# Sheet1.net
KiCad netlist of a schematic drawn in Altium Designer
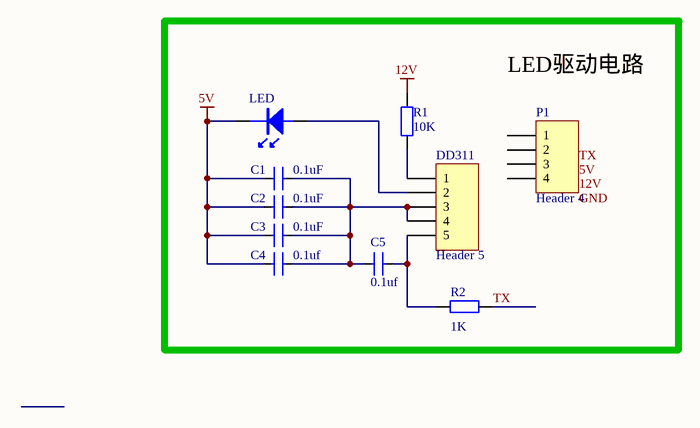
[diagram p0: Sheet1.SchDoc]

(export (version "E")
  (design (tool "Eeschema 10.0.6"))
  (components
    (comp (ref "C1")
      (value "0.1uF")
      (footprint "0805C")
      (description "SMD-CAP")
      (libsource (lib "RCDQLY") (part "C_0.1uF"))
    )
    (comp (ref "C2")
      (value "0.1uF")
      (footprint "0805C")
      (description "SMD-CAP")
      (libsource (lib "RCDQLY") (part "C_0.1uF"))
    )
    (comp (ref "C3")
      (value "0.1uF")
      (footprint "0805C")
      (description "SMD-CAP")
      (libsource (lib "RCDQLY") (part "C_0.1uF"))
    )
    (comp (ref "C4")
      (value "0.1uf")
      (footprint "0805C")
      (description "SMD-CAP")
      (libsource (lib "RCDQLY") (part "C_0.1uF"))
    )
    (comp (ref "C5")
      (value "0.1uf")
      (footprint "0805C")
      (description "SMD-CAP")
      (libsource (lib "RCDQLY") (part "C_0.1uF"))
    )
    (comp (ref "DD311")
      (value "Header 5")
      (footprint "DD311")
      (description "Header, 5-Pin")
      (fields (field (name "PUBLISHER") "Altium Limited"))
      (libsource (lib "Miscellaneous Connectors") (part "Header 5"))
    )
    (comp (ref "LED")
      (value "D-LED")
      (footprint "led")
      (description "LED")
      (libsource (lib "RCDQLY") (part "D-LED"))
    )
    (comp (ref "P1")
      (value "Header 4")
      (footprint "HDR1X4")
      (description "Header, 4-Pin")
      (fields (field (name "PUBLISHER") "Altium Limited"))
      (libsource (lib "Miscellaneous Connectors") (part "Header 4"))
    )
    (comp (ref "R1")
      (value "10K")
      (footprint "0805")
      (description "Resistor")
      (fields (field (name "Comment") "Res2") (field (name "PUBLISHER") "Altium Limited"))
      (libsource (lib "Miscellaneous Devices") (part "Res2"))
    )
    (comp (ref "R2")
      (value "1K")
      (footprint "0805")
      (description "Resistor")
      (fields (field (name "Comment") "Res2") (field (name "PUBLISHER") "Altium Limited"))
      (libsource (lib "") (part "Res2_1"))
    )
  )
  (nets
    (net (code "2") (name "/TX") (class "Default")
      (node (ref "R2") (pin "2") (pinfunction "2_2") (pintype "passive"))
    )
    (net (code "3") (name "5V") (class "Default")
      (node (ref "C1") (pin "1") (pinfunction "1_1") (pintype "passive"))
      (node (ref "C2") (pin "1") (pinfunction "1_1") (pintype "passive"))
      (node (ref "C3") (pin "1") (pinfunction "1_1") (pintype "passive"))
      (node (ref "C4") (pin "1") (pinfunction "1_1") (pintype "passive"))
      (node (ref "LED") (pin "K") (pinfunction "2_K") (pintype "passive"))
    )
    (net (code "4") (name "12V") (class "Default")
      (node (ref "R1") (pin "2") (pinfunction "2_2") (pintype "passive"))
    )
    (net (code "5") (name "Net-(C1-Pad2)") (class "Default")
      (node (ref "C1") (pin "2") (pinfunction "2_2") (pintype "passive"))
      (node (ref "C2") (pin "2") (pinfunction "2_2") (pintype "passive"))
      (node (ref "C3") (pin "2") (pinfunction "2_2") (pintype "passive"))
      (node (ref "C4") (pin "2") (pinfunction "2_2") (pintype "passive"))
      (node (ref "C5") (pin "1") (pinfunction "1_1") (pintype "passive"))
      (node (ref "DD311") (pin "3") (pinfunction "3_3") (pintype "passive"))
      (node (ref "DD311") (pin "4") (pinfunction "4_4") (pintype "passive"))
    )
    (net (code "6") (name "Net-(C5-Pad2)") (class "Default")
      (node (ref "C5") (pin "2") (pinfunction "2_2") (pintype "passive"))
      (node (ref "DD311") (pin "5") (pinfunction "5_5") (pintype "passive"))
      (node (ref "R2") (pin "1") (pinfunction "1_1") (pintype "passive"))
    )
    (net (code "7") (name "Net-(DD311-Pad1)") (class "Default")
      (node (ref "DD311") (pin "1") (pinfunction "1_1") (pintype "passive"))
      (node (ref "R1") (pin "1") (pinfunction "1_1") (pintype "passive"))
    )
    (net (code "8") (name "Net-(LED-1)") (class "Default")
      (node (ref "DD311") (pin "2") (pinfunction "2_2") (pintype "passive"))
      (node (ref "LED") (pin "A") (pinfunction "1_A") (pintype "passive"))
    )
    (net (code "9") (name "unconnected-(P1-Pad1)") (class "Default")
      (node (ref "P1") (pin "1") (pinfunction "1_1") (pintype "passive"))
    )
    (net (code "10") (name "unconnected-(P1-Pad2)") (class "Default")
      (node (ref "P1") (pin "2") (pinfunction "2_2") (pintype "passive"))
    )
    (net (code "11") (name "unconnected-(P1-Pad3)") (class "Default")
      (node (ref "P1") (pin "3") (pinfunction "3_3") (pintype "passive"))
    )
    (net (code "12") (name "unconnected-(P1-Pad4)") (class "Default")
      (node (ref "P1") (pin "4") (pinfunction "4_4") (pintype "passive"))
    )
  )
)
